# USB_TO_UART.net
KiCad netlist of a schematic drawn in Altium Designer
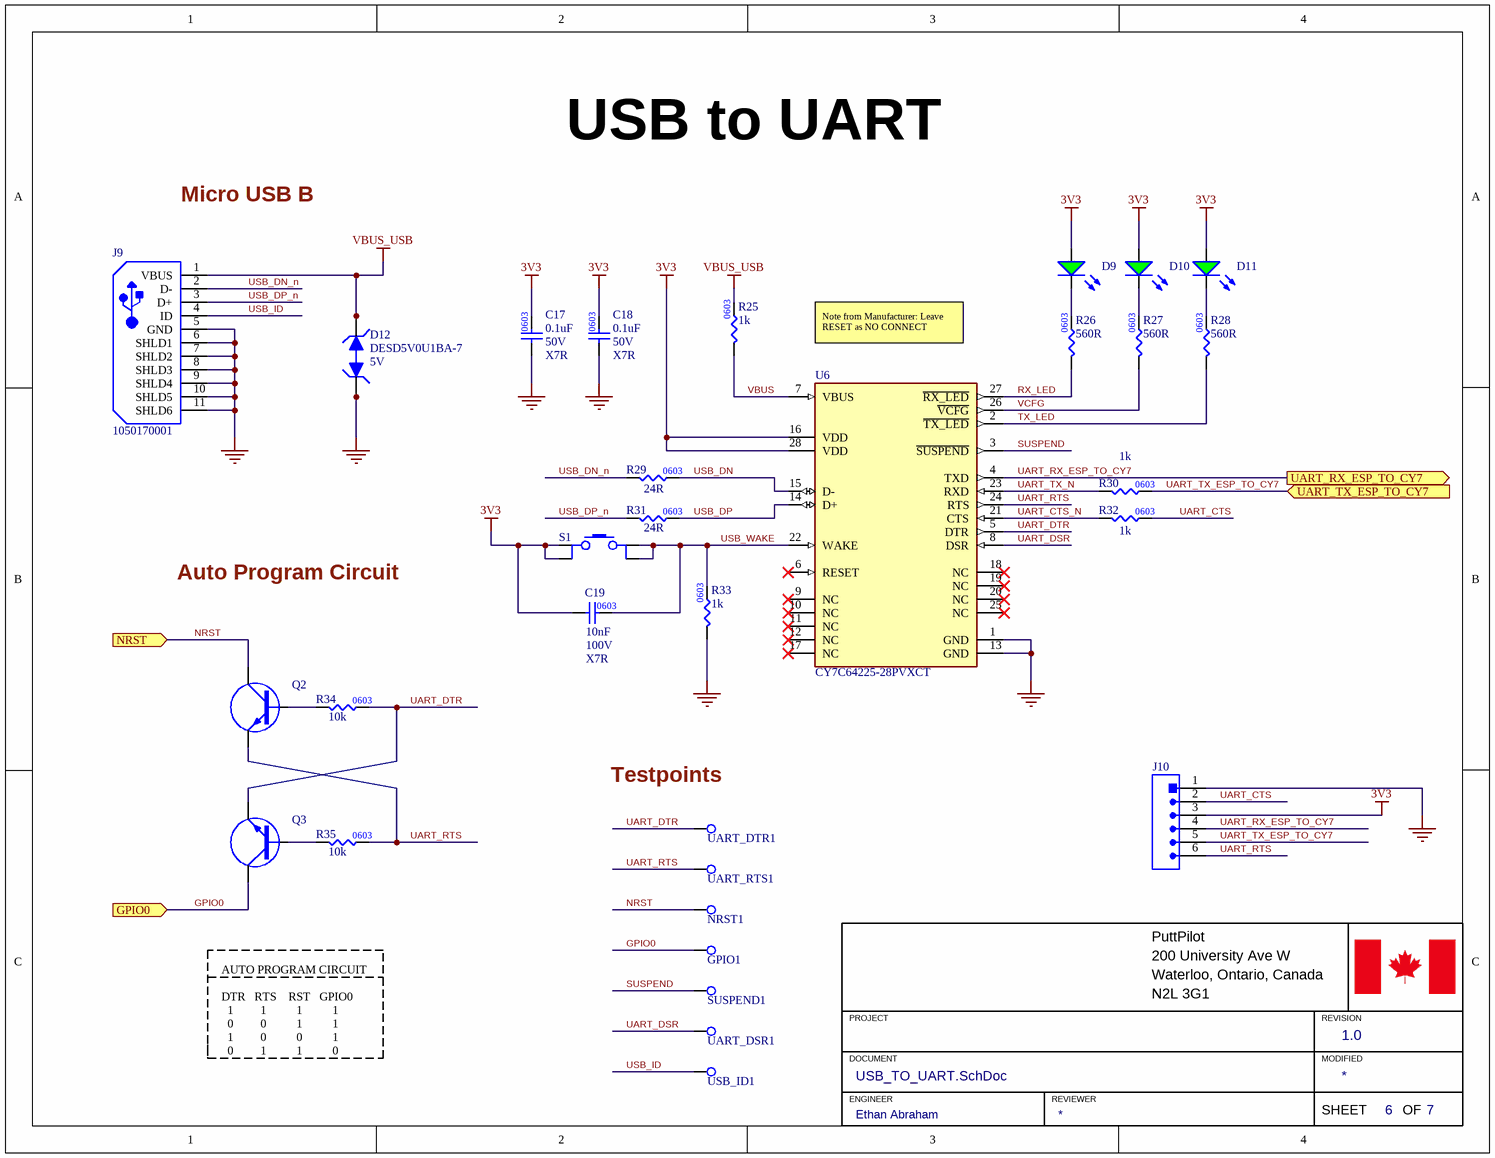
[diagram p0: USB_TO_UART.SchDoc]

(export (version "E")
  (design (tool "Eeschema 10.0.6"))
  (components
    (comp (ref "C17")
      (value "GCJ188R71H104KA12D")
      (footprint ".CAP_0603")
      (description "CAP CER 0.1uF 50V X7R 0603")
      (fields
        (field (name "MANUFACTURER") "Murata")
        (field (name "TEMPERATURE CHARACTERISTICS CODE") "X7R")
        (field (name "RATED DC VOLTAGE (URDC)") "50V")
        (field (name "CAPACITANCE") "0.1uF")
      )
      (libsource (lib "PuttPilot") (part "GCJ188R71H104KA12D"))
    )
    (comp (ref "C18")
      (value "GCJ188R71H104KA12D")
      (footprint ".CAP_0603")
      (description "CAP CER 0.1uF 50V X7R 0603")
      (fields
        (field (name "MANUFACTURER") "Murata")
        (field (name "TEMPERATURE CHARACTERISTICS CODE") "X7R")
        (field (name "RATED DC VOLTAGE (URDC)") "50V")
        (field (name "CAPACITANCE") "0.1uF")
      )
      (libsource (lib "PuttPilot") (part "GCJ188R71H104KA12D"))
    )
    (comp (ref "C19")
      (value "GCM188R72A103KA37D")
      (footprint ".CAP_0603")
      (description "CAP CER 0.01uF 100V X7R")
      (fields
        (field (name "MANUFACTURER") "Murata")
        (field (name "TOLERANCE") "10%")
        (field (name "DIELECTRIC") "X7R")
        (field (name "VOLTAGE RATING") "100V")
        (field (name "CAPACITANCE") "10nF")
      )
      (libsource (lib "PuttPilot") (part "GCM188R72A103KA37D"))
    )
    (comp (ref "D9")
      (value "LTST-C191KGKT")
      (footprint ".LED_0603")
      (description "LED GREEN 2V 0603")
      (fields (field (name "MANUFACTURER") "Vishay Lite-On"))
      (libsource (lib "PuttPilot") (part "LTST-C191KGKT"))
    )
    (comp (ref "D10")
      (value "LTST-C191KGKT")
      (footprint ".LED_0603")
      (description "LED GREEN 2V 0603")
      (fields (field (name "MANUFACTURER") "Vishay Lite-On"))
      (libsource (lib "PuttPilot") (part "LTST-C191KGKT"))
    )
    (comp (ref "D11")
      (value "LTST-C191KGKT")
      (footprint ".LED_0603")
      (description "LED GREEN 2V 0603")
      (fields (field (name "MANUFACTURER") "Vishay Lite-On"))
      (libsource (lib "PuttPilot") (part "LTST-C191KGKT"))
    )
    (comp (ref "D12")
      (value "DESD5V0U1BA-7")
      (footprint "DESD5V0U1BA-7")
      (description "TVS DIODE 5VWM")
      (fields (field (name "MANUFACTURER") "Diodes") (field (name "REP PK REVERSE VOLTAGE-MAX") "5V"))
      (libsource (lib "PuttPilot") (part "DESD5V0U1BA-7"))
    )
    (comp (ref "GPIO1")
      (value "RCWCTE")
      (footprint "RCWCTE")
      (description "SMT Test Point")
      (fields (field (name "MANUFACTURER") "KOA Speer"))
      (libsource (lib "PuttPilot") (part "RCWCTE"))
    )
    (comp (ref "J9")
      (value "1050170001")
      (footprint "USB_MICRO_B")
      (description "CONN USB MICRO B R/A")
      (fields (field (name "MANUFACTURER") "Molex"))
      (libsource (lib "PuttPilot") (part "1050170001"))
    )
    (comp (ref "J10")
      (value "PRPC040SAAN-RC_POS6")
      (footprint "HEADER_6POS_2.54MM")
      (description "CONN HEADER VERT 6POS 2.54MM")
      (libsource (lib "PuttPilot") (part "PRPC040SAAN-RC_POS6"))
    )
    (comp (ref "NRST1")
      (value "RCWCTE")
      (footprint "RCWCTE")
      (description "SMT Test Point")
      (fields (field (name "MANUFACTURER") "KOA Speer"))
      (libsource (lib "PuttPilot") (part "RCWCTE"))
    )
    (comp (ref "Q2")
      (value "MMBT2222A-7-F")
      (footprint ".SOT-23-3")
      (description "NPN BJT 40V 600mA SOT-23")
      (fields (field (name "MANUFACTURER") "Diodes"))
      (libsource (lib "") (part "MMBT2222A-7-F_1"))
    )
    (comp (ref "Q3")
      (value "MMBT2222A-7-F")
      (footprint ".SOT-23-3")
      (description "NPN BJT 40V 600mA SOT-23")
      (fields (field (name "MANUFACTURER") "Diodes"))
      (libsource (lib "PuttPilot") (part "MMBT2222A-7-F"))
    )
    (comp (ref "R25")
      (value "RC0603FR-071KL")
      (footprint ".RES_0603")
      (description "RES 1K OHM 0603")
      (fields
        (field (name "MANUFACTURER") "Yageo")
        (field (name "TOLERANCE") "1%")
        (field (name "RESISTANCE") "1k")
      )
      (libsource (lib "PuttPilot") (part "RC0603FR-071KL"))
    )
    (comp (ref "R26")
      (value "RC0603FR-07560RL")
      (footprint ".RES_0603")
      (description "RES 560 OHM 0603")
      (fields
        (field (name "MANUFACTURER") "Yageo")
        (field (name "TOLERANCE") "1%")
        (field (name "RESISTANCE") "560R")
      )
      (libsource (lib "PuttPilot") (part "RC0603FR-07560RL"))
    )
    (comp (ref "R27")
      (value "RC0603FR-07560RL")
      (footprint ".RES_0603")
      (description "RES 560 OHM 0603")
      (fields
        (field (name "MANUFACTURER") "Yageo")
        (field (name "TOLERANCE") "1%")
        (field (name "RESISTANCE") "560R")
      )
      (libsource (lib "PuttPilot") (part "RC0603FR-07560RL"))
    )
    (comp (ref "R28")
      (value "RC0603FR-07560RL")
      (footprint ".RES_0603")
      (description "RES 560 OHM 0603")
      (fields
        (field (name "MANUFACTURER") "Yageo")
        (field (name "TOLERANCE") "1%")
        (field (name "RESISTANCE") "560R")
      )
      (libsource (lib "PuttPilot") (part "RC0603FR-07560RL"))
    )
    (comp (ref "R29")
      (value "RC0603FR-0724RL")
      (footprint ".RES_0603")
      (description "RES 24 OHM 0603")
      (fields
        (field (name "MANUFACTURER") "Yageo")
        (field (name "TOLERANCE") "1%")
        (field (name "RESISTANCE") "24R")
      )
      (libsource (lib "PuttPilot") (part "RC0603FR-0724RL"))
    )
    (comp (ref "R30")
      (value "RC0603FR-071KL")
      (footprint ".RES_0603")
      (description "RES 1K OHM 0603")
      (fields
        (field (name "MANUFACTURER") "Yageo")
        (field (name "TOLERANCE") "1%")
        (field (name "RESISTANCE") "1k")
      )
      (libsource (lib "PuttPilot") (part "RC0603FR-071KL"))
    )
    (comp (ref "R31")
      (value "RC0603FR-0724RL")
      (footprint ".RES_0603")
      (description "RES 24 OHM 0603")
      (fields
        (field (name "MANUFACTURER") "Yageo")
        (field (name "TOLERANCE") "1%")
        (field (name "RESISTANCE") "24R")
      )
      (libsource (lib "PuttPilot") (part "RC0603FR-0724RL"))
    )
    (comp (ref "R32")
      (value "RC0603FR-071KL")
      (footprint ".RES_0603")
      (description "RES 1K OHM 0603")
      (fields
        (field (name "MANUFACTURER") "Yageo")
        (field (name "TOLERANCE") "1%")
        (field (name "RESISTANCE") "1k")
      )
      (libsource (lib "PuttPilot") (part "RC0603FR-071KL"))
    )
    (comp (ref "R33")
      (value "RC0603FR-071KL")
      (footprint ".RES_0603")
      (description "RES 1K OHM 0603")
      (fields
        (field (name "MANUFACTURER") "Yageo")
        (field (name "TOLERANCE") "1%")
        (field (name "RESISTANCE") "1k")
      )
      (libsource (lib "PuttPilot") (part "RC0603FR-071KL"))
    )
    (comp (ref "R34")
      (value "RC0603FR-0710KL")
      (footprint ".RES_0603")
      (description "RES 10K OHM 0603")
      (fields
        (field (name "MANUFACTURER") "Yageo")
        (field (name "TOLERANCE") "1%")
        (field (name "RESISTANCE") "10k")
      )
      (libsource (lib "PuttPilot") (part "RC0603FR-0710KL"))
    )
    (comp (ref "R35")
      (value "RC0603FR-0710KL")
      (footprint ".RES_0603")
      (description "RES 10K OHM 0603")
      (fields
        (field (name "MANUFACTURER") "Yageo")
        (field (name "TOLERANCE") "1%")
        (field (name "RESISTANCE") "10k")
      )
      (libsource (lib "PuttPilot") (part "RC0603FR-0710KL"))
    )
    (comp (ref "S1")
      (value "PTS647SN38SMTR2LFS")
      (footprint "PTS647SN38SMTR2LFS")
      (description "SWITCH TACTILE SPST-NO 0.05A 12V")
      (fields (field (name "MANUFACTURER") "ITT C&K"))
      (libsource (lib "PuttPilot") (part "PTS647SN38SMTR2LFS"))
    )
    (comp (ref "SUSPEND1")
      (value "RCWCTE")
      (footprint "RCWCTE")
      (description "SMT Test Point")
      (fields (field (name "MANUFACTURER") "KOA Speer"))
      (libsource (lib "PuttPilot") (part "RCWCTE"))
    )
    (comp (ref "U6")
      (value "CY7C64225-28PVXCT")
      (footprint "CY7C64225-28PVXCT")
      (description "USB to UART SOP 28 Pin")
      (fields (field (name "MANUFACTURER") "Infineon"))
      (libsource (lib "PuttPilot") (part "CY7C64225-28PVXCT"))
    )
    (comp (ref "UART_DSR1")
      (value "RCWCTE")
      (footprint "RCWCTE")
      (description "SMT Test Point")
      (fields (field (name "MANUFACTURER") "KOA Speer"))
      (libsource (lib "PuttPilot") (part "RCWCTE"))
    )
    (comp (ref "UART_DTR1")
      (value "RCWCTE")
      (footprint "RCWCTE")
      (description "SMT Test Point")
      (fields (field (name "MANUFACTURER") "KOA Speer"))
      (libsource (lib "PuttPilot") (part "RCWCTE"))
    )
    (comp (ref "UART_RTS1")
      (value "RCWCTE")
      (footprint "RCWCTE")
      (description "SMT Test Point")
      (fields (field (name "MANUFACTURER") "KOA Speer"))
      (libsource (lib "PuttPilot") (part "RCWCTE"))
    )
    (comp (ref "USB_ID1")
      (value "RCWCTE")
      (footprint "RCWCTE")
      (description "SMT Test Point")
      (fields (field (name "MANUFACTURER") "KOA Speer"))
      (libsource (lib "PuttPilot") (part "RCWCTE"))
    )
  )
  (nets
    (net (code "1") (name "/GPIO0") (class "Default")
      (node (ref "GPIO1") (pin "1") (pinfunction "1_1") (pintype "passive"))
      (node (ref "Q3") (pin "2") (pinfunction "Emitter_2") (pintype "passive"))
    )
    (net (code "2") (name "/NRST") (class "Default")
      (node (ref "NRST1") (pin "1") (pinfunction "1_1") (pintype "passive"))
      (node (ref "Q2") (pin "2") (pinfunction "Emitter_2") (pintype "passive"))
    )
    (net (code "3") (name "/RX_LED") (class "Default")
      (node (ref "R26") (pin "1") (pinfunction "1_1") (pintype "passive"))
      (node (ref "U6") (pin "27") (pinfunction "~{RX_LED}_27") (pintype "output"))
    )
    (net (code "4") (name "/SUSPEND") (class "Default")
      (node (ref "SUSPEND1") (pin "1") (pinfunction "1_1") (pintype "passive"))
      (node (ref "U6") (pin "3") (pinfunction "~{SUSPEND}_3") (pintype "output"))
    )
    (net (code "5") (name "/TX_LED") (class "Default")
      (node (ref "R28") (pin "1") (pinfunction "1_1") (pintype "passive"))
      (node (ref "U6") (pin "2") (pinfunction "~{TX_LED}_2") (pintype "output"))
    )
    (net (code "6") (name "/UART_CTS") (class "Default")
      (node (ref "J10") (pin "2") (pinfunction "2_2") (pintype "passive"))
      (node (ref "R32") (pin "2") (pinfunction "2_2") (pintype "passive"))
    )
    (net (code "7") (name "/UART_CTS_N") (class "Default")
      (node (ref "R32") (pin "1") (pinfunction "1_1") (pintype "passive"))
      (node (ref "U6") (pin "21") (pinfunction "CTS_21") (pintype "input"))
    )
    (net (code "8") (name "/UART_DSR") (class "Default")
      (node (ref "U6") (pin "8") (pinfunction "DSR_8") (pintype "input"))
      (node (ref "UART_DSR1") (pin "1") (pinfunction "1_1") (pintype "passive"))
    )
    (net (code "9") (name "/UART_DTR") (class "Default")
      (node (ref "Q3") (pin "3") (pinfunction "Collector_3") (pintype "passive"))
      (node (ref "R34") (pin "2") (pinfunction "2_2") (pintype "passive"))
      (node (ref "U6") (pin "5") (pinfunction "DTR_5") (pintype "output"))
      (node (ref "UART_DTR1") (pin "1") (pinfunction "1_1") (pintype "passive"))
    )
    (net (code "10") (name "/UART_RTS") (class "Default")
      (node (ref "J10") (pin "6") (pinfunction "6_6") (pintype "passive"))
      (node (ref "Q2") (pin "3") (pinfunction "Collector_3") (pintype "passive"))
      (node (ref "R35") (pin "2") (pinfunction "2_2") (pintype "passive"))
      (node (ref "U6") (pin "24") (pinfunction "RTS_24") (pintype "output"))
      (node (ref "UART_RTS1") (pin "1") (pinfunction "1_1") (pintype "passive"))
    )
    (net (code "11") (name "/UART_RX_ESP_TO_CY7") (class "Default")
      (node (ref "J10") (pin "4") (pinfunction "4_4") (pintype "passive"))
      (node (ref "U6") (pin "4") (pinfunction "TXD_4") (pintype "output"))
    )
    (net (code "12") (name "/UART_TX_ESP_TO_CY7") (class "Default")
      (node (ref "J10") (pin "5") (pinfunction "5_5") (pintype "passive"))
      (node (ref "R30") (pin "2") (pinfunction "2_2") (pintype "passive"))
    )
    (net (code "13") (name "/UART_TX_N") (class "Default")
      (node (ref "R30") (pin "1") (pinfunction "1_1") (pintype "passive"))
      (node (ref "U6") (pin "23") (pinfunction "RXD_23") (pintype "input"))
    )
    (net (code "14") (name "/USB_DN") (class "Default")
      (node (ref "R29") (pin "2") (pinfunction "2_2") (pintype "passive"))
      (node (ref "U6") (pin "15") (pinfunction "D-_15") (pintype "bidirectional"))
    )
    (net (code "15") (name "/USB_DN_n") (class "Default")
      (node (ref "J9") (pin "2") (pinfunction "D-_2") (pintype "passive"))
      (node (ref "R29") (pin "1") (pinfunction "1_1") (pintype "passive"))
    )
    (net (code "16") (name "/USB_DP") (class "Default")
      (node (ref "R31") (pin "2") (pinfunction "2_2") (pintype "passive"))
      (node (ref "U6") (pin "14") (pinfunction "D+_14") (pintype "bidirectional"))
    )
    (net (code "17") (name "/USB_DP_n") (class "Default")
      (node (ref "J9") (pin "3") (pinfunction "D+_3") (pintype "passive"))
      (node (ref "R31") (pin "1") (pinfunction "1_1") (pintype "passive"))
    )
    (net (code "18") (name "/USB_ID") (class "Default")
      (node (ref "J9") (pin "4") (pinfunction "ID_4") (pintype "passive"))
      (node (ref "USB_ID1") (pin "1") (pinfunction "1_1") (pintype "passive"))
    )
    (net (code "19") (name "/USB_WAKE") (class "Default")
      (node (ref "C19") (pin "2") (pinfunction "2_2") (pintype "passive"))
      (node (ref "R33") (pin "2") (pinfunction "2_2") (pintype "passive"))
      (node (ref "S1") (pin "3") (pinfunction "3_3") (pintype "passive"))
      (node (ref "S1") (pin "4") (pinfunction "4_4") (pintype "passive"))
      (node (ref "U6") (pin "22") (pinfunction "WAKE_22") (pintype "input"))
    )
    (net (code "20") (name "/VBUS") (class "Default")
      (node (ref "R25") (pin "1") (pinfunction "1_1") (pintype "passive"))
      (node (ref "U6") (pin "7") (pinfunction "VBUS_7") (pintype "input"))
    )
    (net (code "21") (name "/VCFG") (class "Default")
      (node (ref "R27") (pin "1") (pinfunction "1_1") (pintype "passive"))
      (node (ref "U6") (pin "26") (pinfunction "~{VCFG}_26") (pintype "output"))
    )
    (net (code "22") (name "3V3") (class "Default")
      (node (ref "C17") (pin "2") (pinfunction "2_2") (pintype "passive"))
      (node (ref "C18") (pin "2") (pinfunction "2_2") (pintype "passive"))
      (node (ref "C19") (pin "1") (pinfunction "1_1") (pintype "passive"))
      (node (ref "D10") (pin "1") (pinfunction "A_1") (pintype "passive"))
      (node (ref "D11") (pin "1") (pinfunction "A_1") (pintype "passive"))
      (node (ref "D9") (pin "1") (pinfunction "A_1") (pintype "passive"))
      (node (ref "J10") (pin "3") (pinfunction "3_3") (pintype "passive"))
      (node (ref "S1") (pin "1") (pinfunction "1_1") (pintype "passive"))
      (node (ref "S1") (pin "2") (pinfunction "2_2") (pintype "passive"))
      (node (ref "U6") (pin "16") (pinfunction "VDD_16") (pintype "power_in"))
      (node (ref "U6") (pin "28") (pinfunction "VDD_28") (pintype "power_in"))
    )
    (net (code "23") (name "GND") (class "Default")
      (node (ref "C17") (pin "1") (pinfunction "1_1") (pintype "passive"))
      (node (ref "C18") (pin "1") (pinfunction "1_1") (pintype "passive"))
      (node (ref "D12") (pin "1") (pinfunction "Pin_1_1") (pintype "passive"))
      (node (ref "J10") (pin "1") (pinfunction "1_1") (pintype "passive"))
      (node (ref "J9") (pin "10") (pinfunction "SHLD5_10") (pintype "passive"))
      (node (ref "J9") (pin "11") (pinfunction "SHLD6_11") (pintype "passive"))
      (node (ref "J9") (pin "5") (pinfunction "GND_5") (pintype "passive"))
      (node (ref "J9") (pin "6") (pinfunction "SHLD1_6") (pintype "passive"))
      (node (ref "J9") (pin "7") (pinfunction "SHLD2_7") (pintype "passive"))
      (node (ref "J9") (pin "8") (pinfunction "SHLD3_8") (pintype "passive"))
      (node (ref "J9") (pin "9") (pinfunction "SHLD4_9") (pintype "passive"))
      (node (ref "R33") (pin "1") (pinfunction "1_1") (pintype "passive"))
      (node (ref "U6") (pin "1") (pinfunction "GND_1") (pintype "power_in"))
      (node (ref "U6") (pin "13") (pinfunction "GND_13") (pintype "power_in"))
    )
    (net (code "24") (name "Net-(D9-K)") (class "Default")
      (node (ref "D9") (pin "2") (pinfunction "K_2") (pintype "passive"))
      (node (ref "R26") (pin "2") (pinfunction "2_2") (pintype "passive"))
    )
    (net (code "25") (name "Net-(D10-K)") (class "Default")
      (node (ref "D10") (pin "2") (pinfunction "K_2") (pintype "passive"))
      (node (ref "R27") (pin "2") (pinfunction "2_2") (pintype "passive"))
    )
    (net (code "26") (name "Net-(D11-K)") (class "Default")
      (node (ref "D11") (pin "2") (pinfunction "K_2") (pintype "passive"))
      (node (ref "R28") (pin "2") (pinfunction "2_2") (pintype "passive"))
    )
    (net (code "27") (name "Net-(Q2-Base)") (class "Default")
      (node (ref "Q2") (pin "1") (pinfunction "Base_1") (pintype "passive"))
      (node (ref "R34") (pin "1") (pinfunction "1_1") (pintype "passive"))
    )
    (net (code "28") (name "Net-(Q3-Base)") (class "Default")
      (node (ref "Q3") (pin "1") (pinfunction "Base_1") (pintype "passive"))
      (node (ref "R35") (pin "1") (pinfunction "1_1") (pintype "passive"))
    )
    (net (code "29") (name "VBUS_USB") (class "Default")
      (node (ref "D12") (pin "2") (pinfunction "Pin_2_2") (pintype "passive"))
      (node (ref "J9") (pin "1") (pinfunction "VBUS_1") (pintype "passive"))
      (node (ref "R25") (pin "2") (pinfunction "2_2") (pintype "passive"))
    )
    (net (code "30") (name "unconnected-(U6-NC-Pad9)") (class "Default")
      (node (ref "U6") (pin "9") (pinfunction "NC_9") (pintype "passive+no_connect"))
    )
    (net (code "31") (name "unconnected-(U6-NC-Pad10)") (class "Default")
      (node (ref "U6") (pin "10") (pinfunction "NC_10") (pintype "passive+no_connect"))
    )
    (net (code "32") (name "unconnected-(U6-NC-Pad11)") (class "Default")
      (node (ref "U6") (pin "11") (pinfunction "NC_11") (pintype "passive+no_connect"))
    )
    (net (code "33") (name "unconnected-(U6-NC-Pad12)") (class "Default")
      (node (ref "U6") (pin "12") (pinfunction "NC_12") (pintype "passive+no_connect"))
    )
    (net (code "34") (name "unconnected-(U6-NC-Pad17)") (class "Default")
      (node (ref "U6") (pin "17") (pinfunction "NC_17") (pintype "passive+no_connect"))
    )
    (net (code "35") (name "unconnected-(U6-NC-Pad18)") (class "Default")
      (node (ref "U6") (pin "18") (pinfunction "NC_18") (pintype "passive+no_connect"))
    )
    (net (code "36") (name "unconnected-(U6-NC-Pad19)") (class "Default")
      (node (ref "U6") (pin "19") (pinfunction "NC_19") (pintype "passive+no_connect"))
    )
    (net (code "37") (name "unconnected-(U6-NC-Pad20)") (class "Default")
      (node (ref "U6") (pin "20") (pinfunction "NC_20") (pintype "passive+no_connect"))
    )
    (net (code "38") (name "unconnected-(U6-NC-Pad25)") (class "Default")
      (node (ref "U6") (pin "25") (pinfunction "NC_25") (pintype "passive+no_connect"))
    )
    (net (code "39") (name "unconnected-(U6-RESET-Pad6)") (class "Default")
      (node (ref "U6") (pin "6") (pinfunction "RESET_6") (pintype "input+no_connect"))
    )
  )
)
